# Bpod_PortBreakout_r1.net
KiCad netlist of a schematic drawn in EAGLE
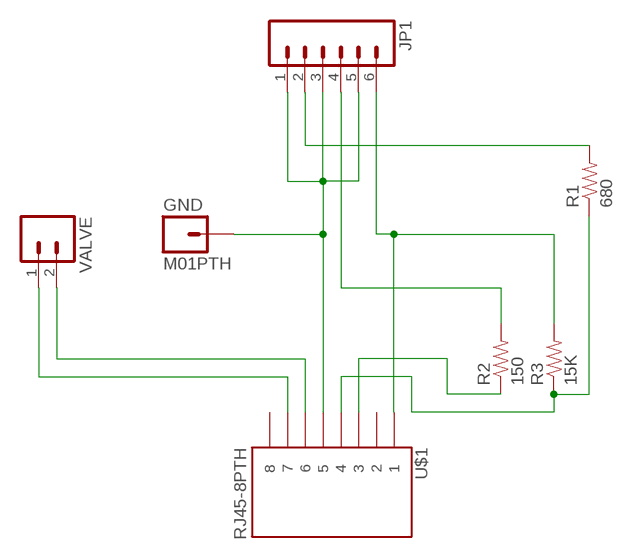
[diagram p0: schematic, sheet 1]

(export (version "E")
  (design (tool "Eeschema 10.0.6"))
  (components
    (comp (ref "GND")
      (value "M01PTH")
      (footprint "eagle-import:1X01")
      (libsource (lib "eagle-import") (part "M01PTH"))
    )
    (comp (ref "JP1")
      (value "M063.5MM-6")
      (footprint "eagle-import:SCREWTERMINAL-3.5MM-6")
      (libsource (lib "eagle-import") (part "M063.5MM-6"))
    )
    (comp (ref "R1")
      (value "680")
      (footprint "eagle-import:AXIAL-0.4")
      (libsource (lib "eagle-import") (part "RESISTORPTH-1/4W"))
    )
    (comp (ref "R2")
      (value "150")
      (footprint "eagle-import:AXIAL-0.4")
      (libsource (lib "eagle-import") (part "RESISTORPTH-1/4W"))
    )
    (comp (ref "R3")
      (value "15K")
      (footprint "eagle-import:AXIAL-0.4")
      (libsource (lib "eagle-import") (part "RESISTORPTH-1/4W"))
    )
    (comp (ref "U$1")
      (value "RJ45-8PTH")
      (footprint "eagle-import:RJ45-8")
      (libsource (lib "eagle-import") (part "RJ45-8PTH"))
    )
    (comp (ref "VALVE")
      (value "M023.5MM_LOCK")
      (footprint "eagle-import:SCREWTERMINAL-3.5MM-2_LOCK")
      (libsource (lib "eagle-import") (part "M023.5MM_LOCK"))
    )
  )
  (nets
    (net (code "1") (name "Net-(GND-Pad1)") (class "Default")
      (node (ref "GND") (pin "1") (pinfunction "1_1") (pintype "passive"))
      (node (ref "JP1") (pin "1") (pinfunction "1_1") (pintype "passive"))
      (node (ref "JP1") (pin "3") (pinfunction "3_3") (pintype "passive"))
      (node (ref "JP1") (pin "5") (pinfunction "5_5") (pintype "passive"))
      (node (ref "U$1") (pin "5") (pinfunction "5_5") (pintype "bidirectional"))
    )
    (net (code "2") (name "Net-(R1-1)") (class "Default")
      (node (ref "R1") (pin "P$1") (pinfunction "1_P$1") (pintype "passive"))
      (node (ref "R3") (pin "P$1") (pinfunction "1_P$1") (pintype "passive"))
      (node (ref "U$1") (pin "4") (pinfunction "4_4") (pintype "bidirectional"))
    )
    (net (code "3") (name "Net-(R1-2)") (class "Default")
      (node (ref "JP1") (pin "2") (pinfunction "2_2") (pintype "passive"))
      (node (ref "R1") (pin "P$2") (pinfunction "2_P$2") (pintype "passive"))
    )
    (net (code "4") (name "Net-(R2-1)") (class "Default")
      (node (ref "R2") (pin "P$1") (pinfunction "1_P$1") (pintype "passive"))
      (node (ref "U$1") (pin "3") (pinfunction "3_3") (pintype "bidirectional"))
    )
    (net (code "5") (name "Net-(R2-2)") (class "Default")
      (node (ref "JP1") (pin "4") (pinfunction "4_4") (pintype "passive"))
      (node (ref "R2") (pin "P$2") (pinfunction "2_P$2") (pintype "passive"))
    )
    (net (code "6") (name "Net-(R3-2)") (class "Default")
      (node (ref "JP1") (pin "6") (pinfunction "6_6") (pintype "passive"))
      (node (ref "R3") (pin "P$2") (pinfunction "2_P$2") (pintype "passive"))
      (node (ref "U$1") (pin "1") (pinfunction "1_1") (pintype "bidirectional"))
    )
    (net (code "7") (name "Net-(U$1-Pad6)") (class "Default")
      (node (ref "U$1") (pin "6") (pinfunction "6_6") (pintype "bidirectional"))
      (node (ref "VALVE") (pin "2") (pinfunction "2_2") (pintype "passive"))
    )
    (net (code "8") (name "Net-(U$1-Pad7)") (class "Default")
      (node (ref "U$1") (pin "7") (pinfunction "7_7") (pintype "bidirectional"))
      (node (ref "VALVE") (pin "1") (pinfunction "1_1") (pintype "passive"))
    )
    (net (code "9") (name "unconnected-(U$1-Pad2)") (class "Default")
      (node (ref "U$1") (pin "2") (pinfunction "2_2") (pintype "bidirectional"))
    )
    (net (code "10") (name "unconnected-(U$1-Pad8)") (class "Default")
      (node (ref "U$1") (pin "8") (pinfunction "8_8") (pintype "bidirectional"))
    )
  )
)
